# Cell_Balancing.net
KiCad netlist of a schematic drawn in Altium Designer
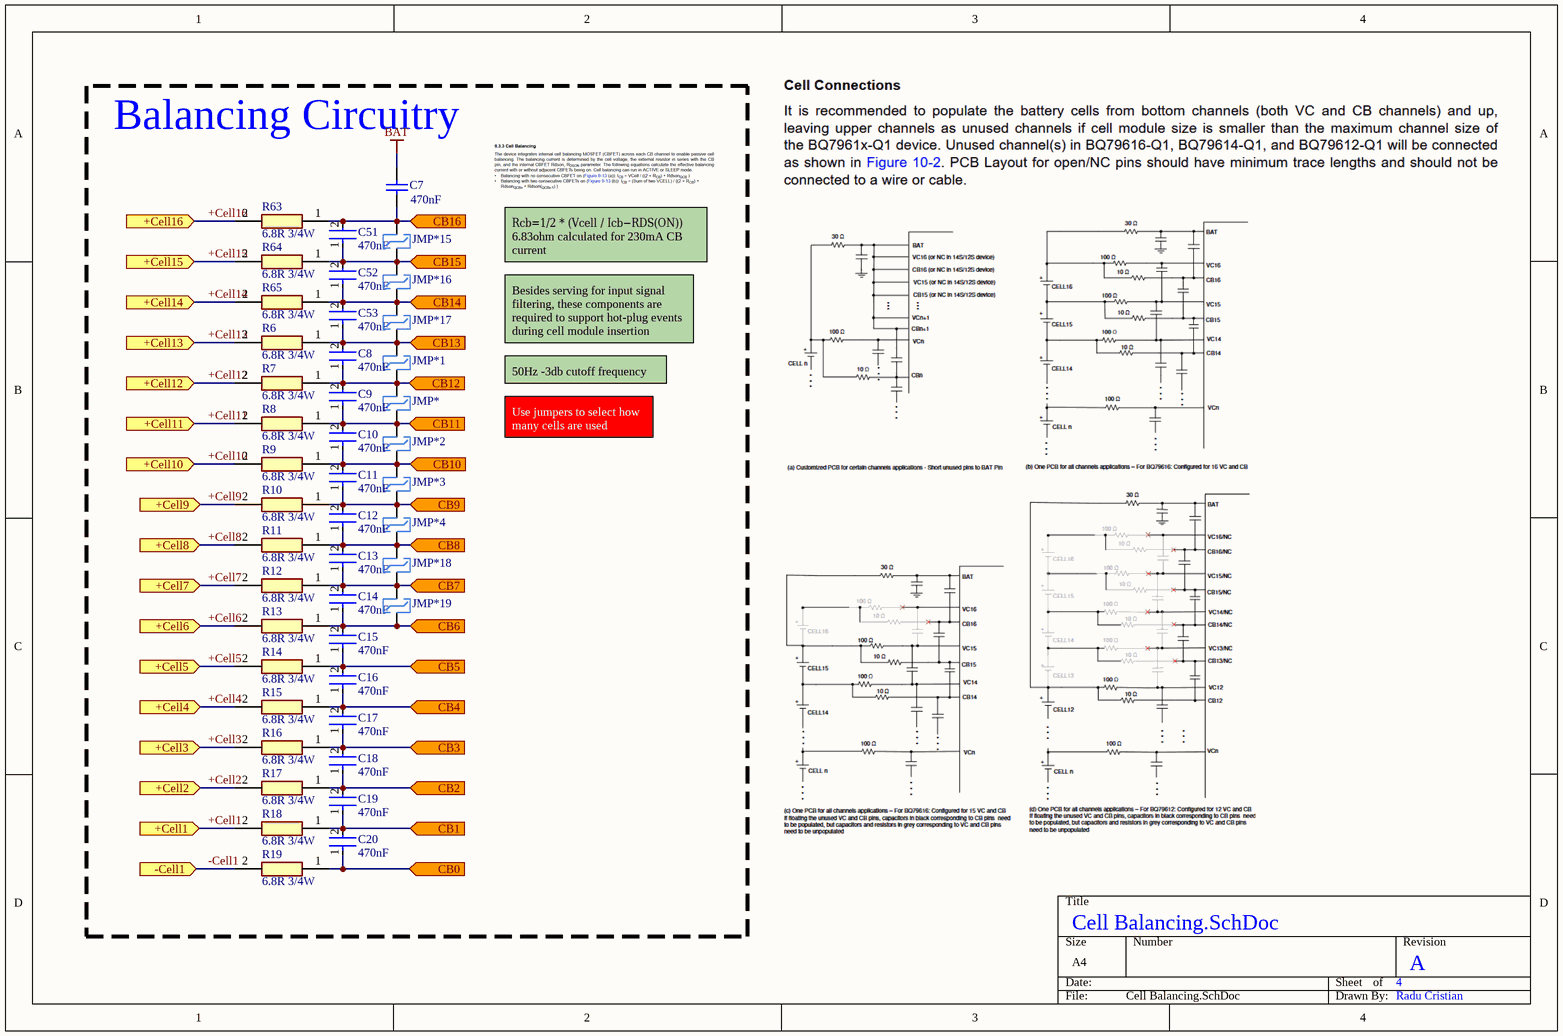
[diagram p0: Cell Balancing.SchDoc]

(export (version "E")
  (design (tool "Eeschema 10.0.6"))
  (components
    (comp (ref "C7")
      (value "470nF")
      (footprint "CAPC0603(1608)100_N")
      (description "CAP 470nF 25V ±20% 0603 (1608 Metric) Thickness 1mm SMD")
      (fields (field (name "TOLERANCE") "Â±20%") (field (name "Comment") "CAP 470nF 25V 0603(1608)"))
      (libsource (lib "Altium Content Vault") (part "CAP"))
    )
    (comp (ref "C8")
      (value "08055C474J4Z2A")
      (footprint "FP-0805-L_2_01_0_2-W_1_25-IPC_C")
      (description "Automotive Ceramic Capacitor, 0805, 470nF, 5%, X7R, 15%, 50V")
      (fields (field (name "CAPACITANCE") "470nF") (field (name "TOLERANCE") "5%"))
      (libsource (lib "Altium Content Vault") (part "b4654b650e69147ec39a6b967a45e02"))
    )
    (comp (ref "C9")
      (value "08055C474J4Z2A")
      (footprint "FP-0805-L_2_01_0_2-W_1_25-IPC_C")
      (description "Automotive Ceramic Capacitor, 0805, 470nF, 5%, X7R, 15%, 50V")
      (fields (field (name "CAPACITANCE") "470nF") (field (name "TOLERANCE") "5%"))
      (libsource (lib "Altium Content Vault") (part "b4654b650e69147ec39a6b967a45e02"))
    )
    (comp (ref "C10")
      (value "08055C474J4Z2A")
      (footprint "FP-0805-L_2_01_0_2-W_1_25-IPC_C")
      (description "Automotive Ceramic Capacitor, 0805, 470nF, 5%, X7R, 15%, 50V")
      (fields (field (name "CAPACITANCE") "470nF") (field (name "TOLERANCE") "5%"))
      (libsource (lib "Altium Content Vault") (part "b4654b650e69147ec39a6b967a45e02"))
    )
    (comp (ref "C11")
      (value "08055C474J4Z2A")
      (footprint "FP-0805-L_2_01_0_2-W_1_25-IPC_C")
      (description "Automotive Ceramic Capacitor, 0805, 470nF, 5%, X7R, 15%, 50V")
      (fields (field (name "CAPACITANCE") "470nF") (field (name "TOLERANCE") "5%"))
      (libsource (lib "Altium Content Vault") (part "b4654b650e69147ec39a6b967a45e02"))
    )
    (comp (ref "C12")
      (value "08055C474J4Z2A")
      (footprint "FP-0805-L_2_01_0_2-W_1_25-IPC_C")
      (description "Automotive Ceramic Capacitor, 0805, 470nF, 5%, X7R, 15%, 50V")
      (fields (field (name "CAPACITANCE") "470nF") (field (name "TOLERANCE") "5%"))
      (libsource (lib "Altium Content Vault") (part "b4654b650e69147ec39a6b967a45e02"))
    )
    (comp (ref "C13")
      (value "08055C474J4Z2A")
      (footprint "FP-0805-L_2_01_0_2-W_1_25-IPC_C")
      (description "Automotive Ceramic Capacitor, 0805, 470nF, 5%, X7R, 15%, 50V")
      (fields (field (name "CAPACITANCE") "470nF") (field (name "TOLERANCE") "5%"))
      (libsource (lib "Altium Content Vault") (part "b4654b650e69147ec39a6b967a45e02"))
    )
    (comp (ref "C14")
      (value "08055C474J4Z2A")
      (footprint "FP-0805-L_2_01_0_2-W_1_25-IPC_C")
      (description "Automotive Ceramic Capacitor, 0805, 470nF, 5%, X7R, 15%, 50V")
      (fields (field (name "CAPACITANCE") "470nF") (field (name "TOLERANCE") "5%"))
      (libsource (lib "Altium Content Vault") (part "b4654b650e69147ec39a6b967a45e02"))
    )
    (comp (ref "C15")
      (value "08055C474J4Z2A")
      (footprint "FP-0805-L_2_01_0_2-W_1_25-IPC_C")
      (description "Automotive Ceramic Capacitor, 0805, 470nF, 5%, X7R, 15%, 50V")
      (fields (field (name "CAPACITANCE") "470nF") (field (name "TOLERANCE") "5%"))
      (libsource (lib "Altium Content Vault") (part "b4654b650e69147ec39a6b967a45e02"))
    )
    (comp (ref "C16")
      (value "08055C474J4Z2A")
      (footprint "FP-0805-L_2_01_0_2-W_1_25-IPC_C")
      (description "Automotive Ceramic Capacitor, 0805, 470nF, 5%, X7R, 15%, 50V")
      (fields (field (name "CAPACITANCE") "470nF") (field (name "TOLERANCE") "5%"))
      (libsource (lib "Altium Content Vault") (part "b4654b650e69147ec39a6b967a45e02"))
    )
    (comp (ref "C17")
      (value "08055C474J4Z2A")
      (footprint "FP-0805-L_2_01_0_2-W_1_25-IPC_C")
      (description "Automotive Ceramic Capacitor, 0805, 470nF, 5%, X7R, 15%, 50V")
      (fields (field (name "CAPACITANCE") "470nF") (field (name "TOLERANCE") "5%"))
      (libsource (lib "Altium Content Vault") (part "b4654b650e69147ec39a6b967a45e02"))
    )
    (comp (ref "C18")
      (value "08055C474J4Z2A")
      (footprint "FP-0805-L_2_01_0_2-W_1_25-IPC_C")
      (description "Automotive Ceramic Capacitor, 0805, 470nF, 5%, X7R, 15%, 50V")
      (fields (field (name "CAPACITANCE") "470nF") (field (name "TOLERANCE") "5%"))
      (libsource (lib "Altium Content Vault") (part "b4654b650e69147ec39a6b967a45e02"))
    )
    (comp (ref "C19")
      (value "08055C474J4Z2A")
      (footprint "FP-0805-L_2_01_0_2-W_1_25-IPC_C")
      (description "Automotive Ceramic Capacitor, 0805, 470nF, 5%, X7R, 15%, 50V")
      (fields (field (name "CAPACITANCE") "470nF") (field (name "TOLERANCE") "5%"))
      (libsource (lib "Altium Content Vault") (part "b4654b650e69147ec39a6b967a45e02"))
    )
    (comp (ref "C20")
      (value "08055C474J4Z2A")
      (footprint "FP-0805-L_2_01_0_2-W_1_25-IPC_C")
      (description "Automotive Ceramic Capacitor, 0805, 470nF, 5%, X7R, 15%, 50V")
      (fields (field (name "CAPACITANCE") "470nF") (field (name "TOLERANCE") "5%"))
      (libsource (lib "Altium Content Vault") (part "b4654b650e69147ec39a6b967a45e02"))
    )
    (comp (ref "C51")
      (value "08055C474J4Z2A")
      (footprint "FP-0805-L_2_01_0_2-W_1_25-IPC_C")
      (description "Automotive Ceramic Capacitor, 0805, 470nF, 5%, X7R, 15%, 50V")
      (fields (field (name "CAPACITANCE") "470nF") (field (name "TOLERANCE") "5%"))
      (libsource (lib "Altium Content Vault") (part "b4654b650e69147ec39a6b967a45e02"))
    )
    (comp (ref "C52")
      (value "08055C474J4Z2A")
      (footprint "FP-0805-L_2_01_0_2-W_1_25-IPC_C")
      (description "Automotive Ceramic Capacitor, 0805, 470nF, 5%, X7R, 15%, 50V")
      (fields (field (name "CAPACITANCE") "470nF") (field (name "TOLERANCE") "5%"))
      (libsource (lib "Altium Content Vault") (part "b4654b650e69147ec39a6b967a45e02"))
    )
    (comp (ref "C53")
      (value "08055C474J4Z2A")
      (footprint "FP-0805-L_2_01_0_2-W_1_25-IPC_C")
      (description "Automotive Ceramic Capacitor, 0805, 470nF, 5%, X7R, 15%, 50V")
      (fields (field (name "CAPACITANCE") "470nF") (field (name "TOLERANCE") "5%"))
      (libsource (lib "Altium Content Vault") (part "b4654b650e69147ec39a6b967a45e02"))
    )
    (comp (ref "JMP*")
      (value "Solder Jumper")
      (footprint "Solder Jumper-Footprint-1")
      (description "2 port solder jumper")
      (libsource (lib "goulash den") (part "Jumper"))
    )
    (comp (ref "JMP*1")
      (value "Solder Jumper")
      (footprint "Solder Jumper-Footprint-1")
      (description "2 port solder jumper")
      (libsource (lib "goulash den") (part "Jumper"))
    )
    (comp (ref "JMP*2")
      (value "Solder Jumper")
      (footprint "Solder Jumper-Footprint-1")
      (description "2 port solder jumper")
      (libsource (lib "goulash den") (part "Jumper"))
    )
    (comp (ref "JMP*3")
      (value "Solder Jumper")
      (footprint "Solder Jumper-Footprint-1")
      (description "2 port solder jumper")
      (libsource (lib "goulash den") (part "Jumper"))
    )
    (comp (ref "JMP*4")
      (value "Solder Jumper")
      (footprint "Solder Jumper-Footprint-1")
      (description "2 port solder jumper")
      (libsource (lib "goulash den") (part "Jumper"))
    )
    (comp (ref "JMP*15")
      (value "Solder Jumper")
      (footprint "Solder Jumper-Footprint-1")
      (description "2 port solder jumper")
      (libsource (lib "goulash den") (part "Jumper"))
    )
    (comp (ref "JMP*16")
      (value "Solder Jumper")
      (footprint "Solder Jumper-Footprint-1")
      (description "2 port solder jumper")
      (libsource (lib "goulash den") (part "Jumper"))
    )
    (comp (ref "JMP*17")
      (value "Solder Jumper")
      (footprint "Solder Jumper-Footprint-1")
      (description "2 port solder jumper")
      (libsource (lib "goulash den") (part "Jumper"))
    )
    (comp (ref "JMP*18")
      (value "Solder Jumper")
      (footprint "Solder Jumper-Footprint-1")
      (description "2 port solder jumper")
      (libsource (lib "goulash den") (part "Jumper"))
    )
    (comp (ref "JMP*19")
      (value "Solder Jumper")
      (footprint "Solder Jumper-Footprint-1")
      (description "2 port solder jumper")
      (libsource (lib "goulash den") (part "Jumper"))
    )
    (comp (ref "R6")
      (value "CRCW12066R80JNEAHP")
      (footprint "PcbLib1:RESC3116X65N")
      (description "Thick Film Resistors - SMD 3/4watt 6.8ohm 5% High Power AEC-Q200")
      (fields (field (name "PARAMETER 1") "6.8R 3/4W"))
      (libsource (lib "Schlib1") (part "CRCW12066R80JNEAHP"))
    )
    (comp (ref "R7")
      (value "CRCW12066R80JNEAHP")
      (footprint "PcbLib1:RESC3116X65N")
      (description "Thick Film Resistors - SMD 3/4watt 6.8ohm 5% High Power AEC-Q200")
      (fields (field (name "PARAMETER 1") "6.8R 3/4W"))
      (libsource (lib "Schlib1") (part "CRCW12066R80JNEAHP"))
    )
    (comp (ref "R8")
      (value "CRCW12066R80JNEAHP")
      (footprint "PcbLib1:RESC3116X65N")
      (description "Thick Film Resistors - SMD 3/4watt 6.8ohm 5% High Power AEC-Q200")
      (fields (field (name "PARAMETER 1") "6.8R 3/4W"))
      (libsource (lib "Schlib1") (part "CRCW12066R80JNEAHP"))
    )
    (comp (ref "R9")
      (value "CRCW12066R80JNEAHP")
      (footprint "PcbLib1:RESC3116X65N")
      (description "Thick Film Resistors - SMD 3/4watt 6.8ohm 5% High Power AEC-Q200")
      (fields (field (name "PARAMETER 1") "6.8R 3/4W"))
      (libsource (lib "Schlib1") (part "CRCW12066R80JNEAHP"))
    )
    (comp (ref "R10")
      (value "CRCW12066R80JNEAHP")
      (footprint "PcbLib1:RESC3116X65N")
      (description "Thick Film Resistors - SMD 3/4watt 6.8ohm 5% High Power AEC-Q200")
      (fields (field (name "PARAMETER 1") "6.8R 3/4W"))
      (libsource (lib "Schlib1") (part "CRCW12066R80JNEAHP"))
    )
    (comp (ref "R11")
      (value "CRCW12066R80JNEAHP")
      (footprint "PcbLib1:RESC3116X65N")
      (description "Thick Film Resistors - SMD 3/4watt 6.8ohm 5% High Power AEC-Q200")
      (fields (field (name "PARAMETER 1") "6.8R 3/4W"))
      (libsource (lib "Schlib1") (part "CRCW12066R80JNEAHP"))
    )
    (comp (ref "R12")
      (value "CRCW12066R80JNEAHP")
      (footprint "PcbLib1:RESC3116X65N")
      (description "Thick Film Resistors - SMD 3/4watt 6.8ohm 5% High Power AEC-Q200")
      (fields (field (name "PARAMETER 1") "6.8R 3/4W"))
      (libsource (lib "Schlib1") (part "CRCW12066R80JNEAHP"))
    )
    (comp (ref "R13")
      (value "CRCW12066R80JNEAHP")
      (footprint "PcbLib1:RESC3116X65N")
      (description "Thick Film Resistors - SMD 3/4watt 6.8ohm 5% High Power AEC-Q200")
      (fields (field (name "PARAMETER 1") "6.8R 3/4W"))
      (libsource (lib "Schlib1") (part "CRCW12066R80JNEAHP"))
    )
    (comp (ref "R14")
      (value "CRCW12066R80JNEAHP")
      (footprint "PcbLib1:RESC3116X65N")
      (description "Thick Film Resistors - SMD 3/4watt 6.8ohm 5% High Power AEC-Q200")
      (fields (field (name "PARAMETER 1") "6.8R 3/4W"))
      (libsource (lib "Schlib1") (part "CRCW12066R80JNEAHP"))
    )
    (comp (ref "R15")
      (value "CRCW12066R80JNEAHP")
      (footprint "PcbLib1:RESC3116X65N")
      (description "Thick Film Resistors - SMD 3/4watt 6.8ohm 5% High Power AEC-Q200")
      (fields (field (name "PARAMETER 1") "6.8R 3/4W"))
      (libsource (lib "Schlib1") (part "CRCW12066R80JNEAHP"))
    )
    (comp (ref "R16")
      (value "CRCW12066R80JNEAHP")
      (footprint "PcbLib1:RESC3116X65N")
      (description "Thick Film Resistors - SMD 3/4watt 6.8ohm 5% High Power AEC-Q200")
      (fields (field (name "PARAMETER 1") "6.8R 3/4W"))
      (libsource (lib "Schlib1") (part "CRCW12066R80JNEAHP"))
    )
    (comp (ref "R17")
      (value "CRCW12066R80JNEAHP")
      (footprint "PcbLib1:RESC3116X65N")
      (description "Thick Film Resistors - SMD 3/4watt 6.8ohm 5% High Power AEC-Q200")
      (fields (field (name "PARAMETER 1") "6.8R 3/4W"))
      (libsource (lib "Schlib1") (part "CRCW12066R80JNEAHP"))
    )
    (comp (ref "R18")
      (value "CRCW12066R80JNEAHP")
      (footprint "PcbLib1:RESC3116X65N")
      (description "Thick Film Resistors - SMD 3/4watt 6.8ohm 5% High Power AEC-Q200")
      (fields (field (name "PARAMETER 1") "6.8R 3/4W"))
      (libsource (lib "Schlib1") (part "CRCW12066R80JNEAHP"))
    )
    (comp (ref "R19")
      (value "CRCW12066R80JNEAHP")
      (footprint "PcbLib1:RESC3116X65N")
      (description "Thick Film Resistors - SMD 3/4watt 6.8ohm 5% High Power AEC-Q200")
      (fields (field (name "PARAMETER 1") "6.8R 3/4W"))
      (libsource (lib "Schlib1") (part "CRCW12066R80JNEAHP"))
    )
    (comp (ref "R63")
      (value "CRCW12066R80JNEAHP")
      (footprint "PcbLib1:RESC3116X65N")
      (description "Thick Film Resistors - SMD 3/4watt 6.8ohm 5% High Power AEC-Q200")
      (fields (field (name "PARAMETER 1") "6.8R 3/4W"))
      (libsource (lib "Schlib1") (part "CRCW12066R80JNEAHP"))
    )
    (comp (ref "R64")
      (value "CRCW12066R80JNEAHP")
      (footprint "PcbLib1:RESC3116X65N")
      (description "Thick Film Resistors - SMD 3/4watt 6.8ohm 5% High Power AEC-Q200")
      (fields (field (name "PARAMETER 1") "6.8R 3/4W"))
      (libsource (lib "Schlib1") (part "CRCW12066R80JNEAHP"))
    )
    (comp (ref "R65")
      (value "CRCW12066R80JNEAHP")
      (footprint "PcbLib1:RESC3116X65N")
      (description "Thick Film Resistors - SMD 3/4watt 6.8ohm 5% High Power AEC-Q200")
      (fields (field (name "PARAMETER 1") "6.8R 3/4W"))
      (libsource (lib "Schlib1") (part "CRCW12066R80JNEAHP"))
    )
  )
  (nets
    (net (code "1") (name "/+Cell1") (class "Default")
      (node (ref "R18") (pin "2") (pinfunction "2_2") (pintype "passive"))
    )
    (net (code "2") (name "/+Cell2") (class "Default")
      (node (ref "R17") (pin "2") (pinfunction "2_2") (pintype "passive"))
    )
    (net (code "3") (name "/+Cell3") (class "Default")
      (node (ref "R16") (pin "2") (pinfunction "2_2") (pintype "passive"))
    )
    (net (code "4") (name "/+Cell4") (class "Default")
      (node (ref "R15") (pin "2") (pinfunction "2_2") (pintype "passive"))
    )
    (net (code "5") (name "/+Cell5") (class "Default")
      (node (ref "R14") (pin "2") (pinfunction "2_2") (pintype "passive"))
    )
    (net (code "6") (name "/+Cell6") (class "Default")
      (node (ref "R13") (pin "2") (pinfunction "2_2") (pintype "passive"))
    )
    (net (code "7") (name "/+Cell7") (class "Default")
      (node (ref "R12") (pin "2") (pinfunction "2_2") (pintype "passive"))
    )
    (net (code "8") (name "/+Cell8") (class "Default")
      (node (ref "R11") (pin "2") (pinfunction "2_2") (pintype "passive"))
    )
    (net (code "9") (name "/+Cell9") (class "Default")
      (node (ref "R10") (pin "2") (pinfunction "2_2") (pintype "passive"))
    )
    (net (code "10") (name "/+Cell10") (class "Default")
      (node (ref "R9") (pin "2") (pinfunction "2_2") (pintype "passive"))
    )
    (net (code "11") (name "/+Cell11") (class "Default")
      (node (ref "R8") (pin "2") (pinfunction "2_2") (pintype "passive"))
    )
    (net (code "12") (name "/+Cell12") (class "Default")
      (node (ref "R7") (pin "2") (pinfunction "2_2") (pintype "passive"))
    )
    (net (code "13") (name "/+Cell13") (class "Default")
      (node (ref "R6") (pin "2") (pinfunction "2_2") (pintype "passive"))
    )
    (net (code "14") (name "/+Cell14") (class "Default")
      (node (ref "R65") (pin "2") (pinfunction "2_2") (pintype "passive"))
    )
    (net (code "15") (name "/+Cell15") (class "Default")
      (node (ref "R64") (pin "2") (pinfunction "2_2") (pintype "passive"))
    )
    (net (code "16") (name "/+Cell16") (class "Default")
      (node (ref "R63") (pin "2") (pinfunction "2_2") (pintype "passive"))
    )
    (net (code "17") (name "/-Cell1") (class "Default")
      (node (ref "R19") (pin "2") (pinfunction "2_2") (pintype "passive"))
    )
    (net (code "18") (name "/CB0") (class "Default")
      (node (ref "C20") (pin "1") (pinfunction "1_1") (pintype "passive"))
      (node (ref "R19") (pin "1") (pinfunction "1_1") (pintype "passive"))
    )
    (net (code "19") (name "/CB1") (class "Default")
      (node (ref "C19") (pin "1") (pinfunction "1_1") (pintype "passive"))
      (node (ref "C20") (pin "2") (pinfunction "2_2") (pintype "passive"))
      (node (ref "R18") (pin "1") (pinfunction "1_1") (pintype "passive"))
    )
    (net (code "20") (name "/CB2") (class "Default")
      (node (ref "C18") (pin "1") (pinfunction "1_1") (pintype "passive"))
      (node (ref "C19") (pin "2") (pinfunction "2_2") (pintype "passive"))
      (node (ref "R17") (pin "1") (pinfunction "1_1") (pintype "passive"))
    )
    (net (code "21") (name "/CB3") (class "Default")
      (node (ref "C17") (pin "1") (pinfunction "1_1") (pintype "passive"))
      (node (ref "C18") (pin "2") (pinfunction "2_2") (pintype "passive"))
      (node (ref "R16") (pin "1") (pinfunction "1_1") (pintype "passive"))
    )
    (net (code "22") (name "/CB4") (class "Default")
      (node (ref "C16") (pin "1") (pinfunction "1_1") (pintype "passive"))
      (node (ref "C17") (pin "2") (pinfunction "2_2") (pintype "passive"))
      (node (ref "R15") (pin "1") (pinfunction "1_1") (pintype "passive"))
    )
    (net (code "23") (name "/CB5") (class "Default")
      (node (ref "C15") (pin "1") (pinfunction "1_1") (pintype "passive"))
      (node (ref "C16") (pin "2") (pinfunction "2_2") (pintype "passive"))
      (node (ref "R14") (pin "1") (pinfunction "1_1") (pintype "passive"))
    )
    (net (code "24") (name "/CB6") (class "Default")
      (node (ref "C14") (pin "1") (pinfunction "1_1") (pintype "passive"))
      (node (ref "C15") (pin "2") (pinfunction "2_2") (pintype "passive"))
      (node (ref "JMP*19") (pin "1") (pinfunction "1_1") (pintype "passive"))
      (node (ref "R13") (pin "1") (pinfunction "1_1") (pintype "passive"))
    )
    (net (code "25") (name "/CB7") (class "Default")
      (node (ref "C13") (pin "1") (pinfunction "1_1") (pintype "passive"))
      (node (ref "C14") (pin "2") (pinfunction "2_2") (pintype "passive"))
      (node (ref "JMP*18") (pin "1") (pinfunction "1_1") (pintype "passive"))
      (node (ref "JMP*19") (pin "2") (pinfunction "2_2") (pintype "passive"))
      (node (ref "R12") (pin "1") (pinfunction "1_1") (pintype "passive"))
    )
    (net (code "26") (name "/CB8") (class "Default")
      (node (ref "C12") (pin "1") (pinfunction "1_1") (pintype "passive"))
      (node (ref "C13") (pin "2") (pinfunction "2_2") (pintype "passive"))
      (node (ref "JMP*18") (pin "2") (pinfunction "2_2") (pintype "passive"))
      (node (ref "JMP*4") (pin "1") (pinfunction "1_1") (pintype "passive"))
      (node (ref "R11") (pin "1") (pinfunction "1_1") (pintype "passive"))
    )
    (net (code "27") (name "/CB9") (class "Default")
      (node (ref "C11") (pin "1") (pinfunction "1_1") (pintype "passive"))
      (node (ref "C12") (pin "2") (pinfunction "2_2") (pintype "passive"))
      (node (ref "JMP*3") (pin "1") (pinfunction "1_1") (pintype "passive"))
      (node (ref "JMP*4") (pin "2") (pinfunction "2_2") (pintype "passive"))
      (node (ref "R10") (pin "1") (pinfunction "1_1") (pintype "passive"))
    )
    (net (code "28") (name "/CB10") (class "Default")
      (node (ref "C10") (pin "1") (pinfunction "1_1") (pintype "passive"))
      (node (ref "C11") (pin "2") (pinfunction "2_2") (pintype "passive"))
      (node (ref "JMP*2") (pin "1") (pinfunction "1_1") (pintype "passive"))
      (node (ref "JMP*3") (pin "2") (pinfunction "2_2") (pintype "passive"))
      (node (ref "R9") (pin "1") (pinfunction "1_1") (pintype "passive"))
    )
    (net (code "29") (name "/CB11") (class "Default")
      (node (ref "C10") (pin "2") (pinfunction "2_2") (pintype "passive"))
      (node (ref "C9") (pin "1") (pinfunction "1_1") (pintype "passive"))
      (node (ref "JMP*") (pin "1") (pinfunction "1_1") (pintype "passive"))
      (node (ref "JMP*2") (pin "2") (pinfunction "2_2") (pintype "passive"))
      (node (ref "R8") (pin "1") (pinfunction "1_1") (pintype "passive"))
    )
    (net (code "30") (name "/CB12") (class "Default")
      (node (ref "C8") (pin "1") (pinfunction "1_1") (pintype "passive"))
      (node (ref "C9") (pin "2") (pinfunction "2_2") (pintype "passive"))
      (node (ref "JMP*") (pin "2") (pinfunction "2_2") (pintype "passive"))
      (node (ref "JMP*1") (pin "1") (pinfunction "1_1") (pintype "passive"))
      (node (ref "R7") (pin "1") (pinfunction "1_1") (pintype "passive"))
    )
    (net (code "31") (name "/CB13") (class "Default")
      (node (ref "C53") (pin "1") (pinfunction "1_1") (pintype "passive"))
      (node (ref "C8") (pin "2") (pinfunction "2_2") (pintype "passive"))
      (node (ref "JMP*1") (pin "2") (pinfunction "2_2") (pintype "passive"))
      (node (ref "JMP*17") (pin "1") (pinfunction "1_1") (pintype "passive"))
      (node (ref "R6") (pin "1") (pinfunction "1_1") (pintype "passive"))
    )
    (net (code "32") (name "/CB14") (class "Default")
      (node (ref "C52") (pin "1") (pinfunction "1_1") (pintype "passive"))
      (node (ref "C53") (pin "2") (pinfunction "2_2") (pintype "passive"))
      (node (ref "JMP*16") (pin "1") (pinfunction "1_1") (pintype "passive"))
      (node (ref "JMP*17") (pin "2") (pinfunction "2_2") (pintype "passive"))
      (node (ref "R65") (pin "1") (pinfunction "1_1") (pintype "passive"))
    )
    (net (code "33") (name "/CB15") (class "Default")
      (node (ref "C51") (pin "1") (pinfunction "1_1") (pintype "passive"))
      (node (ref "C52") (pin "2") (pinfunction "2_2") (pintype "passive"))
      (node (ref "JMP*15") (pin "1") (pinfunction "1_1") (pintype "passive"))
      (node (ref "JMP*16") (pin "2") (pinfunction "2_2") (pintype "passive"))
      (node (ref "R64") (pin "1") (pinfunction "1_1") (pintype "passive"))
    )
    (net (code "34") (name "/CB16") (class "Default")
      (node (ref "C51") (pin "2") (pinfunction "2_2") (pintype "passive"))
      (node (ref "C7") (pin "1") (pinfunction "1_1") (pintype "passive"))
      (node (ref "JMP*15") (pin "2") (pinfunction "2_2") (pintype "passive"))
      (node (ref "R63") (pin "1") (pinfunction "1_1") (pintype "passive"))
    )
    (net (code "35") (name "BAT") (class "Default")
      (node (ref "C7") (pin "2") (pinfunction "2_2") (pintype "passive"))
    )
  )
)
